# Microduino-Core_BLE_20140627.net
KiCad netlist of a schematic drawn in EAGLE
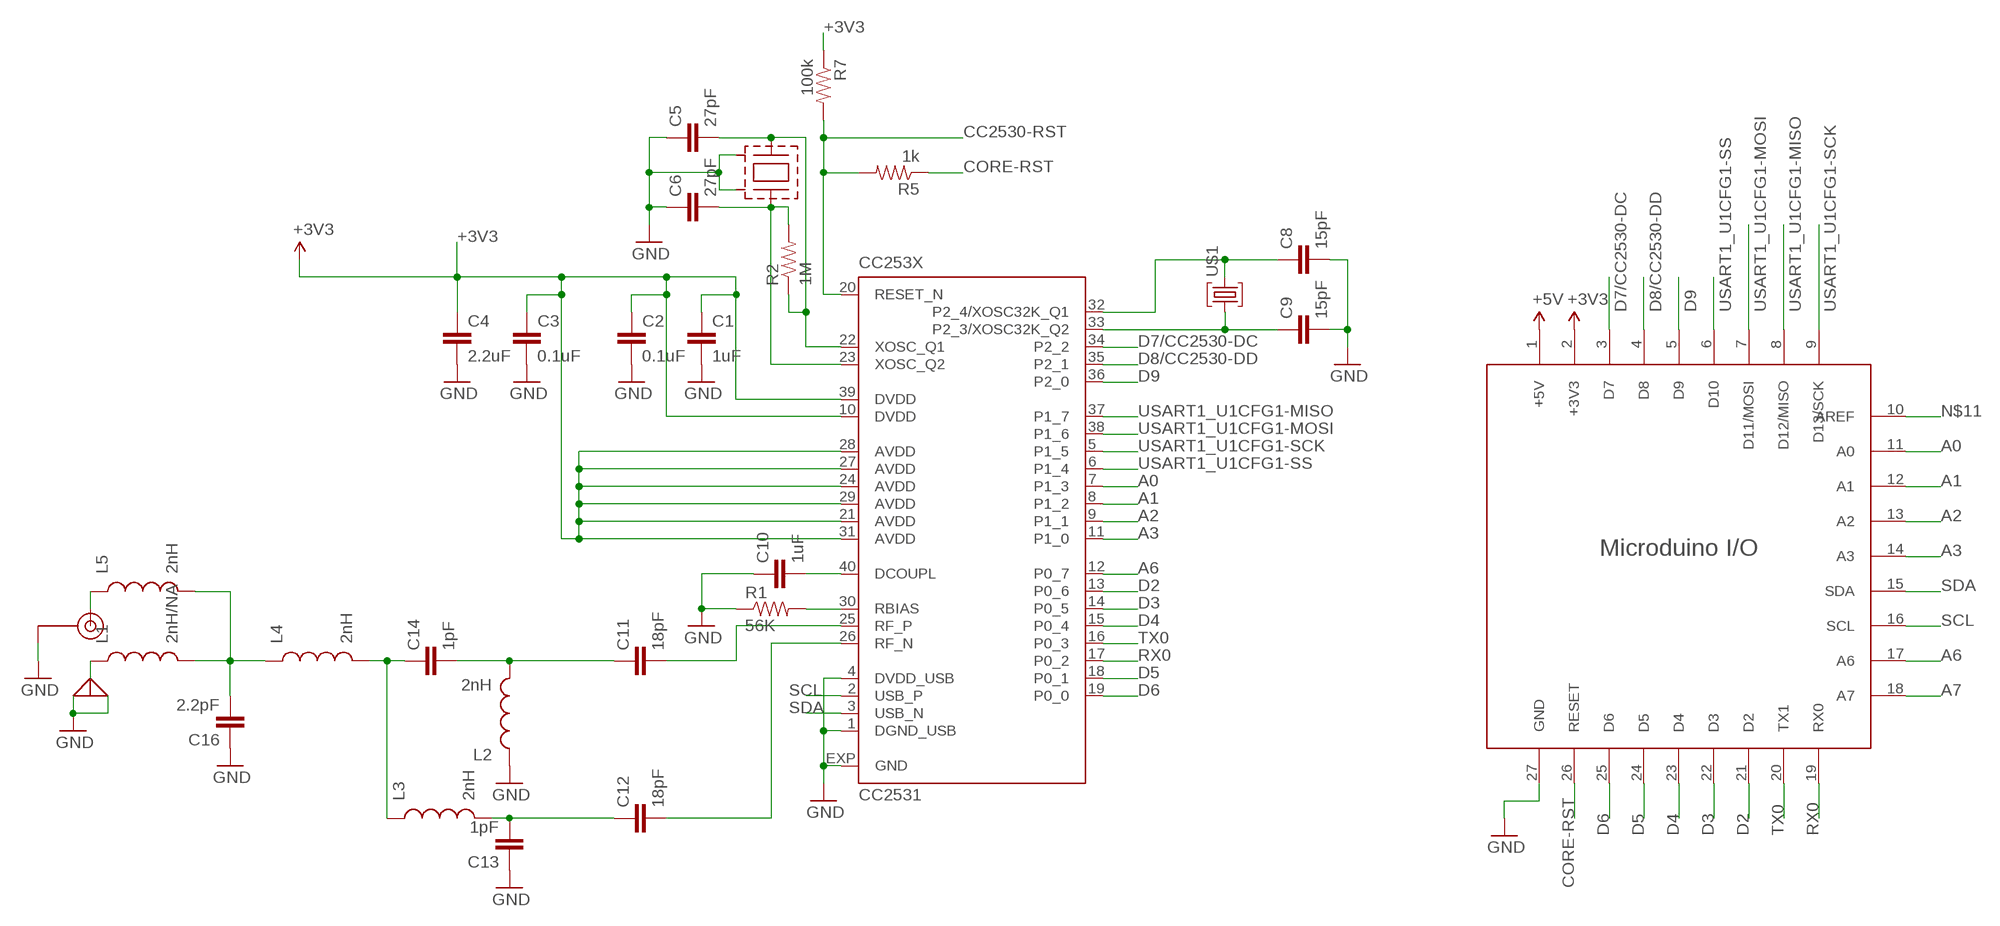
[diagram p0: schematic, sheet 1]

(export (version "E")
  (design (tool "Eeschema 10.0.6"))
  (components
    (comp (ref "C1")
      (value "1uF")
      (footprint "eagle-import:0603-CAP")
      (libsource (lib "eagle-import") (part "CAP0603-CAP"))
    )
    (comp (ref "C2")
      (value "0.1uF")
      (footprint "eagle-import:0402-CAP")
      (libsource (lib "eagle-import") (part "CAP0402-CAP"))
    )
    (comp (ref "C3")
      (value "0.1uF")
      (footprint "eagle-import:0402-CAP")
      (libsource (lib "eagle-import") (part "CAP0402-CAP"))
    )
    (comp (ref "C4")
      (value "2.2uF")
      (footprint "eagle-import:0402-CAP")
      (libsource (lib "eagle-import") (part "CAP0402-CAP"))
    )
    (comp (ref "C5")
      (value "27pF")
      (footprint "eagle-import:0402-CAP")
      (libsource (lib "eagle-import") (part "CAP0402-CAP"))
    )
    (comp (ref "C6")
      (value "27pF")
      (footprint "eagle-import:0402-CAP")
      (libsource (lib "eagle-import") (part "CAP0402-CAP"))
    )
    (comp (ref "C8")
      (value "15pF")
      (footprint "eagle-import:0402-CAP")
      (libsource (lib "eagle-import") (part "CAP0402-CAP"))
    )
    (comp (ref "C9")
      (value "15pF")
      (footprint "eagle-import:0402-CAP")
      (libsource (lib "eagle-import") (part "CAP0402-CAP"))
    )
    (comp (ref "C10")
      (value "1uF")
      (footprint "eagle-import:0603-CAP")
      (libsource (lib "eagle-import") (part "CAP0603-CAP"))
    )
    (comp (ref "C11")
      (value "18pF")
      (footprint "eagle-import:0402-CAP")
      (libsource (lib "eagle-import") (part "CAP0402-CAP"))
    )
    (comp (ref "C12")
      (value "18pF")
      (footprint "eagle-import:0402-CAP")
      (libsource (lib "eagle-import") (part "CAP0402-CAP"))
    )
    (comp (ref "C13")
      (value "1pF")
      (footprint "eagle-import:0402-CAP")
      (libsource (lib "eagle-import") (part "CAP0402-CAP"))
    )
    (comp (ref "C14")
      (value "1pF")
      (footprint "eagle-import:0402-CAP")
      (libsource (lib "eagle-import") (part "CAP0402-CAP"))
    )
    (comp (ref "C16")
      (value "2.2pF")
      (footprint "eagle-import:0402-CAP")
      (libsource (lib "eagle-import") (part "CAP0402-CAP"))
    )
    (comp (ref "CC253X")
      (value "CC2531")
      (footprint "eagle-import:RHA_S-PVQFN-N40")
      (fields (field (name "MPN") "CC2531F256RHAT"))
      (libsource (lib "eagle-import") (part "CC2531"))
    )
    (comp (ref "CRYS.1")
      (value "CRYSTAL-SMD")
      (footprint "eagle-import:CRYSTAL-SMD-3225")
      (libsource (lib "eagle-import") (part "CRYSTAL-SMD"))
    )
    (comp (ref "L1")
      (value "2nH/NA")
      (footprint "eagle-import:C0402")
      (libsource (lib "eagle-import") (part "INDUCTOR0402"))
    )
    (comp (ref "L2")
      (value "2nH")
      (footprint "eagle-import:C0402")
      (libsource (lib "eagle-import") (part "INDUCTOR0402"))
    )
    (comp (ref "L3")
      (value "2nH")
      (footprint "eagle-import:C0402")
      (libsource (lib "eagle-import") (part "INDUCTOR0402"))
    )
    (comp (ref "L4")
      (value "2nH")
      (footprint "eagle-import:C0402")
      (libsource (lib "eagle-import") (part "INDUCTOR0402"))
    )
    (comp (ref "L5")
      (value "2nH")
      (footprint "eagle-import:C0402")
      (libsource (lib "eagle-import") (part "INDUCTOR0402"))
    )
    (comp (ref "R1")
      (value "56K")
      (footprint "eagle-import:0402-RES")
      (libsource (lib "eagle-import") (part "RESISTOR0402-RES"))
    )
    (comp (ref "R2")
      (value "1M")
      (footprint "eagle-import:0402-RES")
      (libsource (lib "eagle-import") (part "RESISTOR0402-RES"))
    )
    (comp (ref "R5")
      (value "1k")
      (footprint "eagle-import:0402-RES")
      (libsource (lib "eagle-import") (part "RESISTOR0402-RES"))
    )
    (comp (ref "R7")
      (value "100k")
      (footprint "eagle-import:0402-RES")
      (libsource (lib "eagle-import") (part "RESISTOR0402-RES"))
    )
    (comp (ref "U$1")
      (value "32.768-3215")
      (footprint "eagle-import:3215-2PIN")
      (libsource (lib "eagle-import") (part "32.768-3215"))
    )
    (comp (ref "U$2")
      (value "ANT2.4G")
      (footprint "eagle-import:ANT2.4G")
      (libsource (lib "eagle-import") (part "ANT2.4G"))
    )
    (comp (ref "U$3")
      (value "ANT-IPEX")
      (footprint "eagle-import:IPEX")
      (libsource (lib "eagle-import") (part "ANT-IPEX"))
    )
    (comp (ref "U$7")
      (value "MICRDUINO-PIN/NORMAL")
      (footprint "eagle-import:27UPIN-NORMAL")
      (libsource (lib "eagle-import") (part "MICRDUINO-PIN/NORMAL"))
    )
  )
  (nets
    (net (code "1") (name "+3V3") (class "Default")
      (node (ref "C1") (pin "1") (pinfunction "1_1") (pintype "passive"))
      (node (ref "C2") (pin "1") (pinfunction "1_1") (pintype "passive"))
      (node (ref "C3") (pin "1") (pinfunction "1_1") (pintype "passive"))
      (node (ref "C4") (pin "1") (pinfunction "1_1") (pintype "passive"))
      (node (ref "CC253X") (pin "10") (pinfunction "DVDD_10") (pintype "power_in"))
      (node (ref "CC253X") (pin "21") (pinfunction "AVDD_21") (pintype "power_in"))
      (node (ref "CC253X") (pin "24") (pinfunction "AVDD_24") (pintype "power_in"))
      (node (ref "CC253X") (pin "27") (pinfunction "AVDD_27") (pintype "power_in"))
      (node (ref "CC253X") (pin "28") (pinfunction "AVDD_28") (pintype "power_in"))
      (node (ref "CC253X") (pin "29") (pinfunction "AVDD_29") (pintype "power_in"))
      (node (ref "CC253X") (pin "31") (pinfunction "AVDD_31") (pintype "power_in"))
      (node (ref "CC253X") (pin "39") (pinfunction "DVDD_39") (pintype "power_in"))
      (node (ref "R7") (pin "1") (pinfunction "1_1") (pintype "passive"))
      (node (ref "U$7") (pin "2") (pinfunction "+3V3_2") (pintype "bidirectional"))
    )
    (net (code "2") (name "+5V") (class "Default")
      (node (ref "U$7") (pin "1") (pinfunction "+5V_1") (pintype "bidirectional"))
    )
    (net (code "3") (name "/A0") (class "Default")
      (node (ref "CC253X") (pin "7") (pinfunction "P1_3_7") (pintype "bidirectional"))
      (node (ref "U$7") (pin "11") (pinfunction "A0_11") (pintype "bidirectional"))
    )
    (net (code "4") (name "/A1") (class "Default")
      (node (ref "CC253X") (pin "8") (pinfunction "P1_2_8") (pintype "bidirectional"))
      (node (ref "U$7") (pin "12") (pinfunction "A1_12") (pintype "bidirectional"))
    )
    (net (code "5") (name "/A2") (class "Default")
      (node (ref "CC253X") (pin "9") (pinfunction "P1_1_9") (pintype "bidirectional"))
      (node (ref "U$7") (pin "13") (pinfunction "A2_13") (pintype "bidirectional"))
    )
    (net (code "6") (name "/A3") (class "Default")
      (node (ref "CC253X") (pin "11") (pinfunction "P1_0_11") (pintype "bidirectional"))
      (node (ref "U$7") (pin "14") (pinfunction "A3_14") (pintype "bidirectional"))
    )
    (net (code "7") (name "/A6") (class "Default")
      (node (ref "CC253X") (pin "12") (pinfunction "P0_7_12") (pintype "bidirectional"))
      (node (ref "U$7") (pin "17") (pinfunction "A6_17") (pintype "bidirectional"))
    )
    (net (code "8") (name "/A7") (class "Default")
      (node (ref "U$7") (pin "18") (pinfunction "A7_18") (pintype "bidirectional"))
    )
    (net (code "9") (name "/CC2530-RST") (class "Default")
      (node (ref "CC253X") (pin "20") (pinfunction "RESET_N_20") (pintype "input"))
      (node (ref "R5") (pin "2") (pinfunction "2_2") (pintype "passive"))
      (node (ref "R7") (pin "2") (pinfunction "2_2") (pintype "passive"))
    )
    (net (code "10") (name "/CORE-RST") (class "Default")
      (node (ref "R5") (pin "1") (pinfunction "1_1") (pintype "passive"))
      (node (ref "U$7") (pin "26") (pinfunction "RESET_26") (pintype "bidirectional"))
    )
    (net (code "11") (name "/D2") (class "Default")
      (node (ref "CC253X") (pin "13") (pinfunction "P0_6_13") (pintype "bidirectional"))
      (node (ref "U$7") (pin "21") (pinfunction "D2_21") (pintype "bidirectional"))
    )
    (net (code "12") (name "/D3") (class "Default")
      (node (ref "CC253X") (pin "14") (pinfunction "P0_5_14") (pintype "bidirectional"))
      (node (ref "U$7") (pin "22") (pinfunction "D3_22") (pintype "bidirectional"))
    )
    (net (code "13") (name "/D4") (class "Default")
      (node (ref "CC253X") (pin "15") (pinfunction "P0_4_15") (pintype "bidirectional"))
      (node (ref "U$7") (pin "23") (pinfunction "D4_23") (pintype "bidirectional"))
    )
    (net (code "14") (name "/D5") (class "Default")
      (node (ref "CC253X") (pin "18") (pinfunction "P0_1_18") (pintype "bidirectional"))
      (node (ref "U$7") (pin "24") (pinfunction "D5_24") (pintype "bidirectional"))
    )
    (net (code "15") (name "/D6") (class "Default")
      (node (ref "CC253X") (pin "19") (pinfunction "P0_0_19") (pintype "bidirectional"))
      (node (ref "U$7") (pin "25") (pinfunction "D6_25") (pintype "bidirectional"))
    )
    (net (code "16") (name "/D7{slash}CC2530-DC") (class "Default")
      (node (ref "CC253X") (pin "34") (pinfunction "P2_2_34") (pintype "bidirectional"))
      (node (ref "U$7") (pin "3") (pinfunction "D7_3") (pintype "bidirectional"))
    )
    (net (code "17") (name "/D8{slash}CC2530-DD") (class "Default")
      (node (ref "CC253X") (pin "35") (pinfunction "P2_1_35") (pintype "bidirectional"))
      (node (ref "U$7") (pin "4") (pinfunction "D8_4") (pintype "bidirectional"))
    )
    (net (code "18") (name "/D9") (class "Default")
      (node (ref "CC253X") (pin "36") (pinfunction "P2_0_36") (pintype "bidirectional"))
      (node (ref "U$7") (pin "5") (pinfunction "D9_5") (pintype "bidirectional"))
    )
    (net (code "19") (name "/N$11") (class "Default")
      (node (ref "U$7") (pin "10") (pinfunction "AREF_10") (pintype "bidirectional"))
    )
    (net (code "20") (name "/RX0") (class "Default")
      (node (ref "CC253X") (pin "17") (pinfunction "P0_2_17") (pintype "bidirectional"))
      (node (ref "U$7") (pin "19") (pinfunction "RX0_19") (pintype "bidirectional"))
    )
    (net (code "21") (name "/SCL") (class "Default")
      (node (ref "CC253X") (pin "2") (pinfunction "USB_P_2") (pintype "bidirectional"))
      (node (ref "U$7") (pin "16") (pinfunction "SCL_16") (pintype "bidirectional"))
    )
    (net (code "22") (name "/SDA") (class "Default")
      (node (ref "CC253X") (pin "3") (pinfunction "USB_N_3") (pintype "bidirectional"))
      (node (ref "U$7") (pin "15") (pinfunction "SDA_15") (pintype "bidirectional"))
    )
    (net (code "23") (name "/TX0") (class "Default")
      (node (ref "CC253X") (pin "16") (pinfunction "P0_3_16") (pintype "bidirectional"))
      (node (ref "U$7") (pin "20") (pinfunction "TX1_20") (pintype "bidirectional"))
    )
    (net (code "24") (name "/USART1_U1CFG1-MISO") (class "Default")
      (node (ref "CC253X") (pin "37") (pinfunction "P1_7_37") (pintype "bidirectional"))
      (node (ref "U$7") (pin "8") (pinfunction "D12/MISO_8") (pintype "bidirectional"))
    )
    (net (code "25") (name "/USART1_U1CFG1-MOSI") (class "Default")
      (node (ref "CC253X") (pin "38") (pinfunction "P1_6_38") (pintype "bidirectional"))
      (node (ref "U$7") (pin "7") (pinfunction "D11/MOSI_7") (pintype "bidirectional"))
    )
    (net (code "26") (name "/USART1_U1CFG1-SCK") (class "Default")
      (node (ref "CC253X") (pin "5") (pinfunction "P1_5_5") (pintype "bidirectional"))
      (node (ref "U$7") (pin "9") (pinfunction "D13/SCK_9") (pintype "bidirectional"))
    )
    (net (code "27") (name "/USART1_U1CFG1-SS") (class "Default")
      (node (ref "CC253X") (pin "6") (pinfunction "P1_4_6") (pintype "bidirectional"))
      (node (ref "U$7") (pin "6") (pinfunction "D10_6") (pintype "bidirectional"))
    )
    (net (code "28") (name "GND") (class "Default")
      (node (ref "C1") (pin "2") (pinfunction "2_2") (pintype "passive"))
      (node (ref "C10") (pin "1") (pinfunction "1_1") (pintype "passive"))
      (node (ref "C13") (pin "1") (pinfunction "1_1") (pintype "passive"))
      (node (ref "C16") (pin "1") (pinfunction "1_1") (pintype "passive"))
      (node (ref "C2") (pin "2") (pinfunction "2_2") (pintype "passive"))
      (node (ref "C3") (pin "2") (pinfunction "2_2") (pintype "passive"))
      (node (ref "C4") (pin "2") (pinfunction "2_2") (pintype "passive"))
      (node (ref "C5") (pin "1") (pinfunction "1_1") (pintype "passive"))
      (node (ref "C6") (pin "1") (pinfunction "1_1") (pintype "passive"))
      (node (ref "C8") (pin "2") (pinfunction "2_2") (pintype "passive"))
      (node (ref "C9") (pin "2") (pinfunction "2_2") (pintype "passive"))
      (node (ref "CC253X") (pin "1") (pinfunction "DGND_USB_1") (pintype "power_in"))
      (node (ref "CC253X") (pin "4") (pinfunction "DVDD_USB_4") (pintype "power_in"))
      (node (ref "CC253X") (pin "EXP") (pinfunction "GND_EXP") (pintype "passive"))
      (node (ref "CRYS.1") (pin "2") (pinfunction "2_2") (pintype "bidirectional"))
      (node (ref "CRYS.1") (pin "4") (pinfunction "4_4") (pintype "bidirectional"))
      (node (ref "L2") (pin "1") (pinfunction "1_1") (pintype "passive"))
      (node (ref "R1") (pin "1") (pinfunction "1_1") (pintype "passive"))
      (node (ref "U$2") (pin "GND") (pinfunction "GND2_GND") (pintype "bidirectional"))
      (node (ref "U$3") (pin "1") (pinfunction "GND1_1") (pintype "bidirectional"))
      (node (ref "U$3") (pin "2") (pinfunction "GND2_2") (pintype "bidirectional"))
      (node (ref "U$7") (pin "27") (pinfunction "GND_27") (pintype "bidirectional"))
    )
    (net (code "29") (name "Net-(C11-Pad1)") (class "Default")
      (node (ref "C11") (pin "1") (pinfunction "1_1") (pintype "passive"))
      (node (ref "C14") (pin "2") (pinfunction "2_2") (pintype "passive"))
      (node (ref "L2") (pin "2") (pinfunction "2_2") (pintype "passive"))
    )
    (net (code "30") (name "Net-(C12-Pad1)") (class "Default")
      (node (ref "C12") (pin "1") (pinfunction "1_1") (pintype "passive"))
      (node (ref "C13") (pin "2") (pinfunction "2_2") (pintype "passive"))
      (node (ref "L3") (pin "2") (pinfunction "2_2") (pintype "passive"))
    )
    (net (code "31") (name "Net-(C14-Pad1)") (class "Default")
      (node (ref "C14") (pin "1") (pinfunction "1_1") (pintype "passive"))
      (node (ref "L3") (pin "1") (pinfunction "1_1") (pintype "passive"))
      (node (ref "L4") (pin "2") (pinfunction "2_2") (pintype "passive"))
    )
    (net (code "32") (name "Net-(C16-Pad2)") (class "Default")
      (node (ref "C16") (pin "2") (pinfunction "2_2") (pintype "passive"))
      (node (ref "L1") (pin "2") (pinfunction "2_2") (pintype "passive"))
      (node (ref "L4") (pin "1") (pinfunction "1_1") (pintype "passive"))
      (node (ref "L5") (pin "2") (pinfunction "2_2") (pintype "passive"))
    )
    (net (code "33") (name "Net-(CC253X-DCOUPL)") (class "Default")
      (node (ref "C10") (pin "2") (pinfunction "2_2") (pintype "passive"))
      (node (ref "CC253X") (pin "40") (pinfunction "DCOUPL_40") (pintype "power_in"))
    )
    (net (code "34") (name "Net-(CC253X-P2_3{slash}XOSC32K_Q2)") (class "Default")
      (node (ref "C9") (pin "1") (pinfunction "1_1") (pintype "passive"))
      (node (ref "CC253X") (pin "33") (pinfunction "P2_3/XOSC32K_Q2_33") (pintype "bidirectional"))
      (node (ref "U$1") (pin "P$1") (pinfunction "1_P$1") (pintype "passive"))
    )
    (net (code "35") (name "Net-(CC253X-P2_4{slash}XOSC32K_Q1)") (class "Default")
      (node (ref "C8") (pin "1") (pinfunction "1_1") (pintype "passive"))
      (node (ref "CC253X") (pin "32") (pinfunction "P2_4/XOSC32K_Q1_32") (pintype "bidirectional"))
      (node (ref "U$1") (pin "P$2") (pinfunction "3_P$2") (pintype "passive"))
    )
    (net (code "36") (name "Net-(CC253X-RBIAS)") (class "Default")
      (node (ref "CC253X") (pin "30") (pinfunction "RBIAS_30") (pintype "bidirectional"))
      (node (ref "R1") (pin "2") (pinfunction "2_2") (pintype "passive"))
    )
    (net (code "37") (name "Net-(CC253X-RF_N)") (class "Default")
      (node (ref "C12") (pin "2") (pinfunction "2_2") (pintype "passive"))
      (node (ref "CC253X") (pin "26") (pinfunction "RF_N_26") (pintype "bidirectional"))
    )
    (net (code "38") (name "Net-(CC253X-RF_P)") (class "Default")
      (node (ref "C11") (pin "2") (pinfunction "2_2") (pintype "passive"))
      (node (ref "CC253X") (pin "25") (pinfunction "RF_P_25") (pintype "bidirectional"))
    )
    (net (code "39") (name "Net-(CC253X-XOSC_Q1)") (class "Default")
      (node (ref "C5") (pin "2") (pinfunction "2_2") (pintype "passive"))
      (node (ref "CC253X") (pin "22") (pinfunction "XOSC_Q1_22") (pintype "bidirectional"))
      (node (ref "CRYS.1") (pin "1") (pinfunction "1_1") (pintype "bidirectional"))
      (node (ref "R2") (pin "1") (pinfunction "1_1") (pintype "passive"))
    )
    (net (code "40") (name "Net-(CC253X-XOSC_Q2)") (class "Default")
      (node (ref "C6") (pin "2") (pinfunction "2_2") (pintype "passive"))
      (node (ref "CC253X") (pin "23") (pinfunction "XOSC_Q2_23") (pintype "bidirectional"))
      (node (ref "CRYS.1") (pin "3") (pinfunction "3_3") (pintype "bidirectional"))
      (node (ref "R2") (pin "2") (pinfunction "2_2") (pintype "passive"))
    )
    (net (code "41") (name "Net-(U$2-IN)") (class "Default")
      (node (ref "L5") (pin "1") (pinfunction "1_1") (pintype "passive"))
      (node (ref "U$2") (pin "ANT") (pinfunction "IN_ANT") (pintype "bidirectional"))
    )
    (net (code "42") (name "Net-(U$3-ANT)") (class "Default")
      (node (ref "L1") (pin "1") (pinfunction "1_1") (pintype "passive"))
      (node (ref "U$3") (pin "3") (pinfunction "ANT_3") (pintype "bidirectional"))
    )
  )
)
